# schematicv1_0.net
KiCad netlist of a schematic drawn in EAGLE
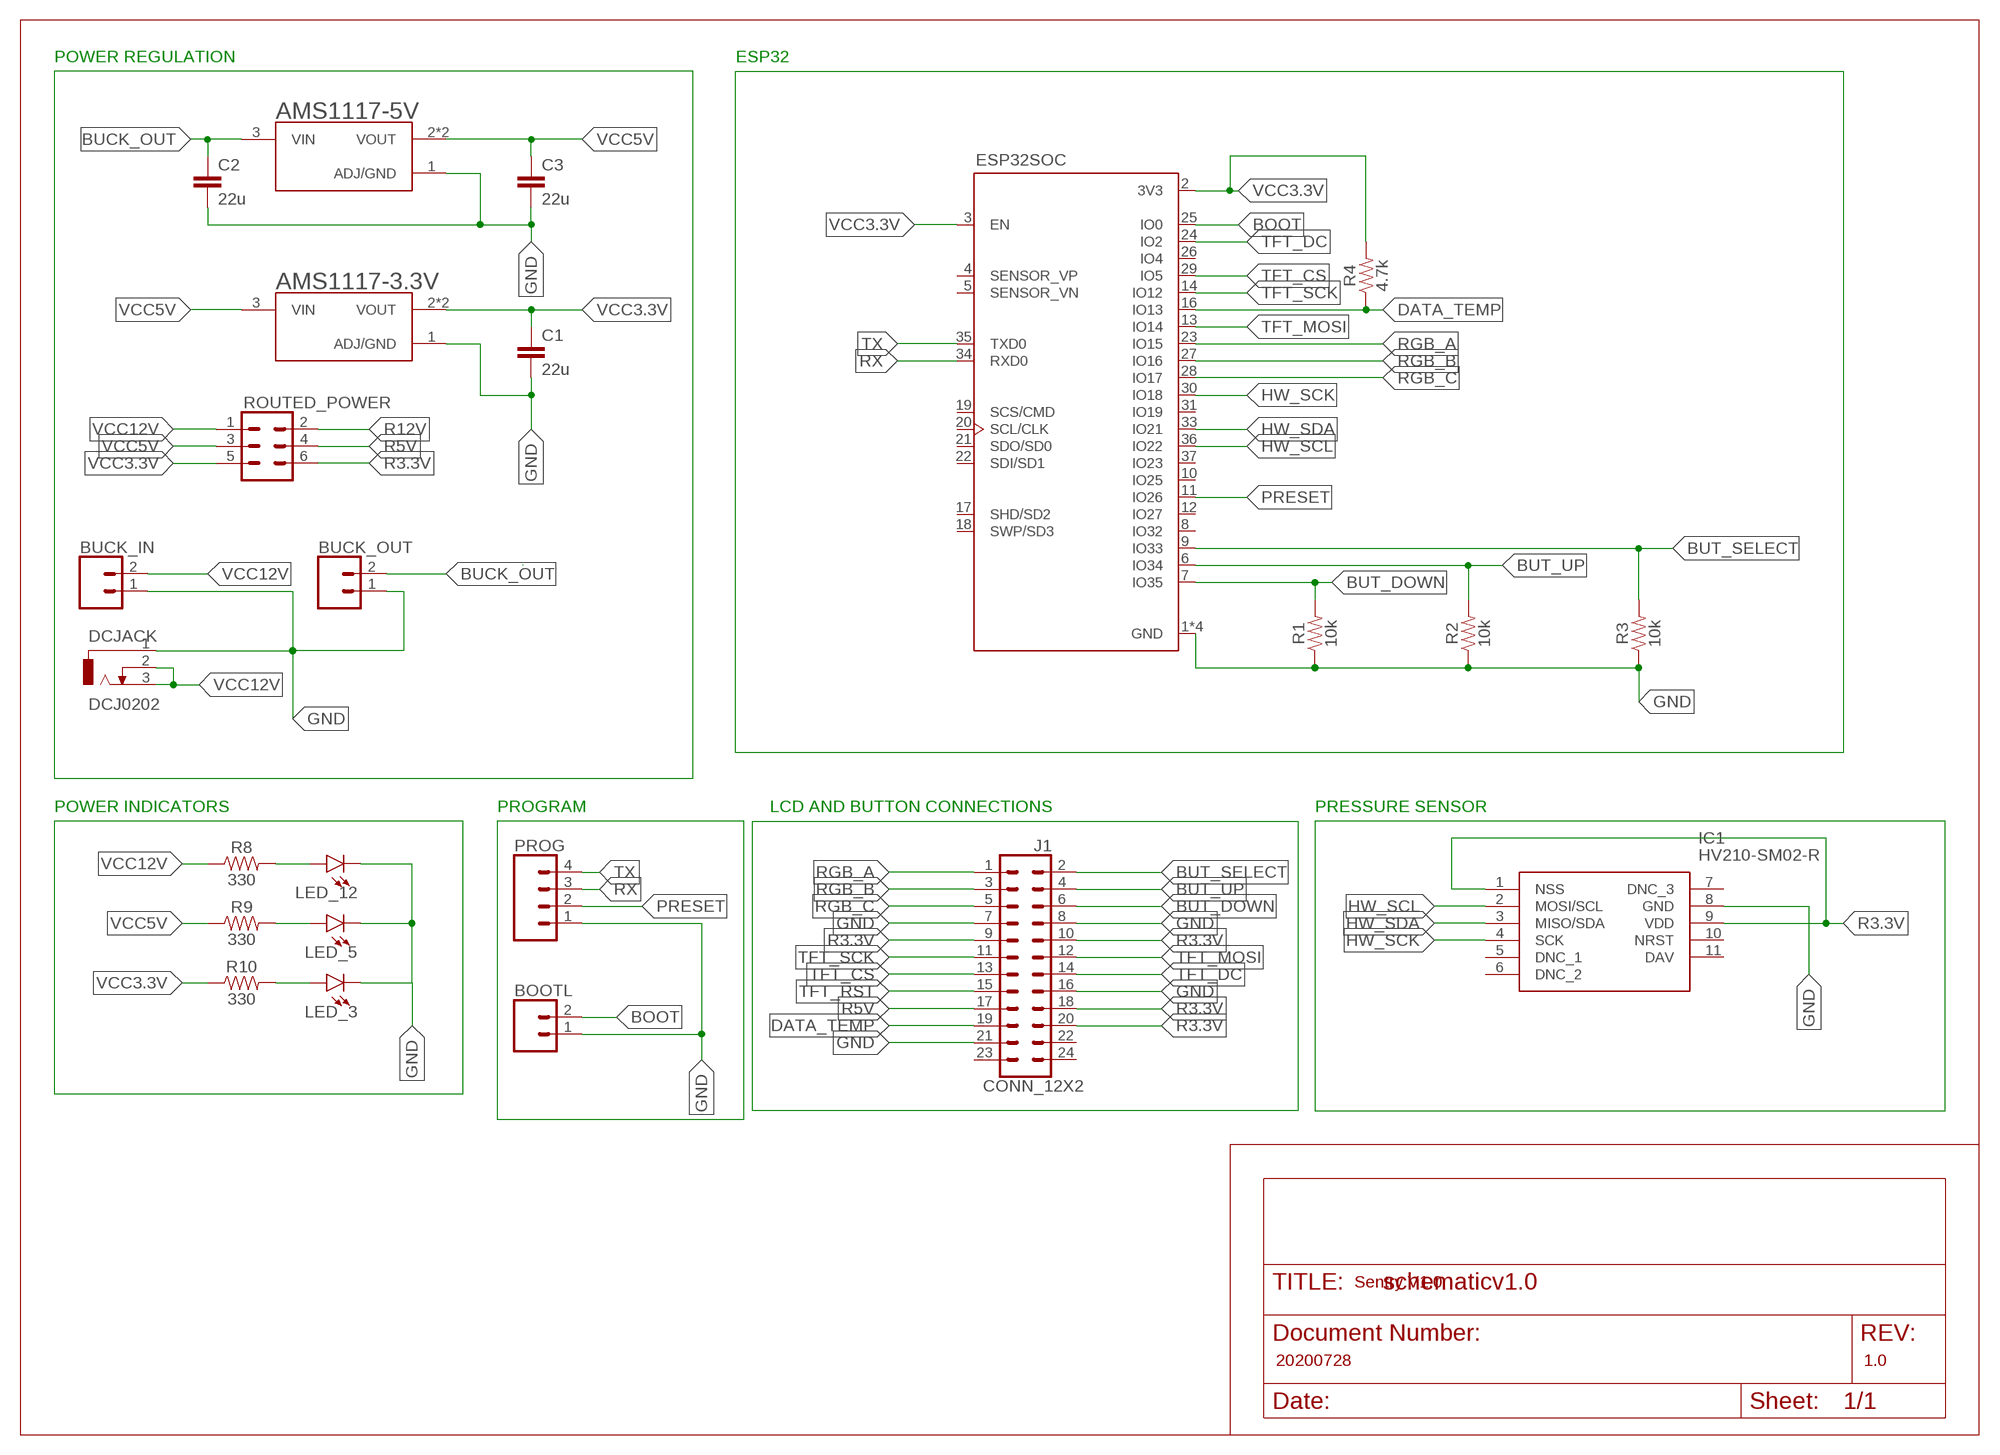
[diagram p0: schematic, sheet 1]

(export (version "E")
  (design (tool "Eeschema 10.0.6"))
  (components
    (comp (ref "AMS1117-3.3V")
      (value "AMS1117")
      (footprint "eagle-import:SOT229P700X180-4N")
      (fields (field (name "MF") "Seeed Technology"))
      (libsource (lib "eagle-import") (part "AMS1117"))
    )
    (comp (ref "AMS1117-5V")
      (value "AMS1117")
      (footprint "eagle-import:SOT229P700X180-4N")
      (fields (field (name "MF") "Seeed Technology"))
      (libsource (lib "eagle-import") (part "AMS1117"))
    )
    (comp (ref "BOOTL")
      (value "CONN_02")
      (footprint "eagle-import:1X02")
      (libsource (lib "eagle-import") (part "CONN_02"))
    )
    (comp (ref "BUCK_IN")
      (value "CONN_02")
      (footprint "eagle-import:1X02")
      (libsource (lib "eagle-import") (part "CONN_02"))
    )
    (comp (ref "BUCK_OUT")
      (value "CONN_02")
      (footprint "eagle-import:1X02")
      (libsource (lib "eagle-import") (part "CONN_02"))
    )
    (comp (ref "C1")
      (value "22u")
      (footprint "eagle-import:1206")
      (libsource (lib "eagle-import") (part "CAP-1206"))
    )
    (comp (ref "C2")
      (value "22u")
      (footprint "eagle-import:1206")
      (libsource (lib "eagle-import") (part "CAP-1206"))
    )
    (comp (ref "C3")
      (value "22u")
      (footprint "eagle-import:1206")
      (libsource (lib "eagle-import") (part "CAP-1206"))
    )
    (comp (ref "DCJACK")
      (value "DCJ0202")
      (footprint "eagle-import:DCJ0202")
      (libsource (lib "eagle-import") (part "DCJ0202"))
    )
    (comp (ref "ESP32SOC")
      (value "ESP32-WROOM-32D")
      (footprint "eagle-import:MODULE_ESP32-WROOM-32D")
      (fields (field (name "MF") "Espressif Systems"))
      (libsource (lib "eagle-import") (part "ESP32-WROOM-32D"))
    )
    (comp (ref "IC1")
      (value "HV210-SM02-R")
      (footprint "eagle-import:HV210SM02R")
      (fields (field (name "MOUSER_PART_NUMBER") "211-HV210-SM02-R"))
      (libsource (lib "eagle-import") (part "HV210-SM02-R"))
    )
    (comp (ref "J1")
      (value "CONN_12X2")
      (footprint "eagle-import:2X12")
      (libsource (lib "eagle-import") (part "CONN_12X2"))
    )
    (comp (ref "LED_3")
      (value "LED1206")
      (footprint "eagle-import:LED-1206")
      (libsource (lib "eagle-import") (part "LED1206"))
    )
    (comp (ref "LED_5")
      (value "LED1206")
      (footprint "eagle-import:LED-1206")
      (libsource (lib "eagle-import") (part "LED1206"))
    )
    (comp (ref "LED_12")
      (value "LED1206")
      (footprint "eagle-import:LED-1206")
      (libsource (lib "eagle-import") (part "LED1206"))
    )
    (comp (ref "PROG")
      (value "CONN_04PTH")
      (footprint "eagle-import:1X04")
      (libsource (lib "eagle-import") (part "CONN_04PTH"))
    )
    (comp (ref "R1")
      (value "10k")
      (footprint "eagle-import:1206")
      (libsource (lib "eagle-import") (part "RESISTOR1206"))
    )
    (comp (ref "R2")
      (value "10k")
      (footprint "eagle-import:1206")
      (libsource (lib "eagle-import") (part "RESISTOR1206"))
    )
    (comp (ref "R3")
      (value "10k")
      (footprint "eagle-import:1206")
      (libsource (lib "eagle-import") (part "RESISTOR1206"))
    )
    (comp (ref "R4")
      (value "4.7k")
      (footprint "eagle-import:1206")
      (libsource (lib "eagle-import") (part "RESISTOR1206"))
    )
    (comp (ref "R8")
      (value "330")
      (footprint "eagle-import:1206")
      (libsource (lib "eagle-import") (part "RESISTOR1206"))
    )
    (comp (ref "R9")
      (value "330")
      (footprint "eagle-import:1206")
      (libsource (lib "eagle-import") (part "RESISTOR1206"))
    )
    (comp (ref "R10")
      (value "330")
      (footprint "eagle-import:1206")
      (libsource (lib "eagle-import") (part "RESISTOR1206"))
    )
    (comp (ref "ROUTED_POWER")
      (value "CONN_03X2FEMALE")
      (footprint "eagle-import:2X3")
      (libsource (lib "eagle-import") (part "CONN_03X2FEMALE"))
    )
  )
  (nets
    (net (code "1") (name "BOOT") (class "Default")
      (node (ref "BOOTL") (pin "2") (pinfunction "2_2") (pintype "passive"))
      (node (ref "ESP32SOC") (pin "25") (pinfunction "IO0_25") (pintype "bidirectional"))
    )
    (net (code "2") (name "BUCK_OUT") (class "Default")
      (node (ref "AMS1117-5V") (pin "3") (pinfunction "VIN_3") (pintype "input"))
      (node (ref "BUCK_OUT") (pin "2") (pinfunction "2_2") (pintype "passive"))
      (node (ref "C2") (pin "1") (pinfunction "1_1") (pintype "passive"))
    )
    (net (code "3") (name "BUT_DOWN") (class "Default")
      (node (ref "ESP32SOC") (pin "7") (pinfunction "IO35_7") (pintype "bidirectional"))
      (node (ref "J1") (pin "6") (pinfunction "6_6") (pintype "passive"))
      (node (ref "R1") (pin "2") (pinfunction "2_2") (pintype "passive"))
    )
    (net (code "4") (name "BUT_SELECT") (class "Default")
      (node (ref "ESP32SOC") (pin "9") (pinfunction "IO33_9") (pintype "bidirectional"))
      (node (ref "J1") (pin "2") (pinfunction "2_2") (pintype "passive"))
      (node (ref "R3") (pin "2") (pinfunction "2_2") (pintype "passive"))
    )
    (net (code "5") (name "BUT_UP") (class "Default")
      (node (ref "ESP32SOC") (pin "6") (pinfunction "IO34_6") (pintype "bidirectional"))
      (node (ref "J1") (pin "4") (pinfunction "4_4") (pintype "passive"))
      (node (ref "R2") (pin "2") (pinfunction "2_2") (pintype "passive"))
    )
    (net (code "6") (name "DATA_TEMP") (class "Default")
      (node (ref "ESP32SOC") (pin "16") (pinfunction "IO13_16") (pintype "bidirectional"))
      (node (ref "J1") (pin "19") (pinfunction "19_19") (pintype "passive"))
      (node (ref "R4") (pin "1") (pinfunction "1_1") (pintype "passive"))
    )
    (net (code "7") (name "GND") (class "Default")
      (node (ref "AMS1117-3.3V") (pin "1") (pinfunction "ADJ/GND_1") (pintype "power_in"))
      (node (ref "AMS1117-5V") (pin "1") (pinfunction "ADJ/GND_1") (pintype "power_in"))
      (node (ref "BOOTL") (pin "1") (pinfunction "1_1") (pintype "passive"))
      (node (ref "BUCK_IN") (pin "1") (pinfunction "1_1") (pintype "passive"))
      (node (ref "BUCK_OUT") (pin "1") (pinfunction "1_1") (pintype "passive"))
      (node (ref "C1") (pin "2") (pinfunction "2_2") (pintype "passive"))
      (node (ref "C2") (pin "2") (pinfunction "2_2") (pintype "passive"))
      (node (ref "C3") (pin "2") (pinfunction "2_2") (pintype "passive"))
      (node (ref "DCJACK") (pin "1") (pinfunction "1_1") (pintype "passive"))
      (node (ref "ESP32SOC") (pin "1") (pinfunction "GND_1") (pintype "power_in"))
      (node (ref "ESP32SOC") (pin "15") (pinfunction "GND_15") (pintype "power_in"))
      (node (ref "ESP32SOC") (pin "38") (pinfunction "GND_38") (pintype "power_in"))
      (node (ref "ESP32SOC") (pin "39") (pinfunction "GND_39") (pintype "power_in"))
      (node (ref "IC1") (pin "8") (pinfunction "GND_8") (pintype "bidirectional"))
      (node (ref "J1") (pin "16") (pinfunction "16_16") (pintype "passive"))
      (node (ref "J1") (pin "21") (pinfunction "21_21") (pintype "passive"))
      (node (ref "J1") (pin "7") (pinfunction "7_7") (pintype "passive"))
      (node (ref "J1") (pin "8") (pinfunction "8_8") (pintype "passive"))
      (node (ref "LED_12") (pin "C") (pinfunction "C_C") (pintype "passive"))
      (node (ref "LED_3") (pin "C") (pinfunction "C_C") (pintype "passive"))
      (node (ref "LED_5") (pin "C") (pinfunction "C_C") (pintype "passive"))
      (node (ref "PROG") (pin "1") (pinfunction "1_1") (pintype "passive"))
      (node (ref "R1") (pin "1") (pinfunction "1_1") (pintype "passive"))
      (node (ref "R2") (pin "1") (pinfunction "1_1") (pintype "passive"))
      (node (ref "R3") (pin "1") (pinfunction "1_1") (pintype "passive"))
    )
    (net (code "8") (name "HW_SCK") (class "Default")
      (node (ref "ESP32SOC") (pin "30") (pinfunction "IO18_30") (pintype "bidirectional"))
      (node (ref "IC1") (pin "4") (pinfunction "SCK_4") (pintype "bidirectional"))
    )
    (net (code "9") (name "HW_SCL") (class "Default")
      (node (ref "ESP32SOC") (pin "36") (pinfunction "IO22_36") (pintype "bidirectional"))
      (node (ref "IC1") (pin "2") (pinfunction "MOSI/SCL_2") (pintype "bidirectional"))
    )
    (net (code "10") (name "HW_SDA") (class "Default")
      (node (ref "ESP32SOC") (pin "33") (pinfunction "IO21_33") (pintype "bidirectional"))
      (node (ref "IC1") (pin "3") (pinfunction "MISO/SDA_3") (pintype "bidirectional"))
    )
    (net (code "11") (name "Net-(LED_3-PadA)") (class "Default")
      (node (ref "LED_3") (pin "A") (pinfunction "A_A") (pintype "passive"))
      (node (ref "R10") (pin "2") (pinfunction "2_2") (pintype "passive"))
    )
    (net (code "12") (name "Net-(LED_5-PadA)") (class "Default")
      (node (ref "LED_5") (pin "A") (pinfunction "A_A") (pintype "passive"))
      (node (ref "R9") (pin "2") (pinfunction "2_2") (pintype "passive"))
    )
    (net (code "13") (name "Net-(LED_12-PadA)") (class "Default")
      (node (ref "LED_12") (pin "A") (pinfunction "A_A") (pintype "passive"))
      (node (ref "R8") (pin "2") (pinfunction "2_2") (pintype "passive"))
    )
    (net (code "14") (name "PRESET") (class "Default")
      (node (ref "ESP32SOC") (pin "11") (pinfunction "IO26_11") (pintype "bidirectional"))
      (node (ref "PROG") (pin "2") (pinfunction "2_2") (pintype "passive"))
    )
    (net (code "15") (name "R3.3V") (class "Default")
      (node (ref "IC1") (pin "1") (pinfunction "NSS_1") (pintype "bidirectional"))
      (node (ref "IC1") (pin "9") (pinfunction "VDD_9") (pintype "bidirectional"))
      (node (ref "J1") (pin "10") (pinfunction "10_10") (pintype "passive"))
      (node (ref "J1") (pin "18") (pinfunction "18_18") (pintype "passive"))
      (node (ref "J1") (pin "20") (pinfunction "20_20") (pintype "passive"))
      (node (ref "J1") (pin "9") (pinfunction "9_9") (pintype "passive"))
      (node (ref "ROUTED_POWER") (pin "6") (pinfunction "6_6") (pintype "bidirectional"))
    )
    (net (code "16") (name "R5V") (class "Default")
      (node (ref "J1") (pin "17") (pinfunction "17_17") (pintype "passive"))
      (node (ref "ROUTED_POWER") (pin "4") (pinfunction "4_4") (pintype "bidirectional"))
    )
    (net (code "17") (name "R12V") (class "Default")
      (node (ref "ROUTED_POWER") (pin "2") (pinfunction "2_2") (pintype "bidirectional"))
    )
    (net (code "18") (name "RGB_A") (class "Default")
      (node (ref "ESP32SOC") (pin "23") (pinfunction "IO15_23") (pintype "bidirectional"))
      (node (ref "J1") (pin "1") (pinfunction "1_1") (pintype "passive"))
    )
    (net (code "19") (name "RGB_B") (class "Default")
      (node (ref "ESP32SOC") (pin "27") (pinfunction "IO16_27") (pintype "bidirectional"))
      (node (ref "J1") (pin "3") (pinfunction "3_3") (pintype "passive"))
    )
    (net (code "20") (name "RGB_C") (class "Default")
      (node (ref "ESP32SOC") (pin "28") (pinfunction "IO17_28") (pintype "bidirectional"))
      (node (ref "J1") (pin "5") (pinfunction "5_5") (pintype "passive"))
    )
    (net (code "21") (name "RX") (class "Default")
      (node (ref "ESP32SOC") (pin "34") (pinfunction "RXD0_34") (pintype "bidirectional"))
      (node (ref "PROG") (pin "3") (pinfunction "3_3") (pintype "passive"))
    )
    (net (code "22") (name "TFT_CS") (class "Default")
      (node (ref "ESP32SOC") (pin "29") (pinfunction "IO5_29") (pintype "bidirectional"))
      (node (ref "J1") (pin "13") (pinfunction "13_13") (pintype "passive"))
    )
    (net (code "23") (name "TFT_DC") (class "Default")
      (node (ref "ESP32SOC") (pin "24") (pinfunction "IO2_24") (pintype "bidirectional"))
      (node (ref "J1") (pin "14") (pinfunction "14_14") (pintype "passive"))
    )
    (net (code "24") (name "TFT_MOSI") (class "Default")
      (node (ref "ESP32SOC") (pin "13") (pinfunction "IO14_13") (pintype "bidirectional"))
      (node (ref "J1") (pin "12") (pinfunction "12_12") (pintype "passive"))
    )
    (net (code "25") (name "TFT_RST") (class "Default")
      (node (ref "J1") (pin "15") (pinfunction "15_15") (pintype "passive"))
    )
    (net (code "26") (name "TFT_SCK") (class "Default")
      (node (ref "ESP32SOC") (pin "14") (pinfunction "IO12_14") (pintype "bidirectional"))
      (node (ref "J1") (pin "11") (pinfunction "11_11") (pintype "passive"))
    )
    (net (code "27") (name "TX") (class "Default")
      (node (ref "ESP32SOC") (pin "35") (pinfunction "TXD0_35") (pintype "bidirectional"))
      (node (ref "PROG") (pin "4") (pinfunction "4_4") (pintype "passive"))
    )
    (net (code "28") (name "VCC3.3V") (class "Default")
      (node (ref "AMS1117-3.3V") (pin "2") (pinfunction "VOUT_2") (pintype "output"))
      (node (ref "AMS1117-3.3V") (pin "4") (pinfunction "VOUT_4") (pintype "output"))
      (node (ref "C1") (pin "1") (pinfunction "1_1") (pintype "passive"))
      (node (ref "ESP32SOC") (pin "2") (pinfunction "3V3_2") (pintype "power_in"))
      (node (ref "ESP32SOC") (pin "3") (pinfunction "EN_3") (pintype "input"))
      (node (ref "R10") (pin "1") (pinfunction "1_1") (pintype "passive"))
      (node (ref "R4") (pin "2") (pinfunction "2_2") (pintype "passive"))
      (node (ref "ROUTED_POWER") (pin "5") (pinfunction "5_5") (pintype "bidirectional"))
    )
    (net (code "29") (name "VCC5V") (class "Default")
      (node (ref "AMS1117-3.3V") (pin "3") (pinfunction "VIN_3") (pintype "input"))
      (node (ref "AMS1117-5V") (pin "2") (pinfunction "VOUT_2") (pintype "output"))
      (node (ref "AMS1117-5V") (pin "4") (pinfunction "VOUT_4") (pintype "output"))
      (node (ref "C3") (pin "1") (pinfunction "1_1") (pintype "passive"))
      (node (ref "R9") (pin "1") (pinfunction "1_1") (pintype "passive"))
      (node (ref "ROUTED_POWER") (pin "3") (pinfunction "3_3") (pintype "bidirectional"))
    )
    (net (code "30") (name "VCC12V") (class "Default")
      (node (ref "BUCK_IN") (pin "2") (pinfunction "2_2") (pintype "passive"))
      (node (ref "DCJACK") (pin "2") (pinfunction "2_2") (pintype "passive"))
      (node (ref "DCJACK") (pin "3") (pinfunction "3_3") (pintype "passive"))
      (node (ref "R8") (pin "1") (pinfunction "1_1") (pintype "passive"))
      (node (ref "ROUTED_POWER") (pin "1") (pinfunction "1_1") (pintype "bidirectional"))
    )
    (net (code "31") (name "unconnected-(ESP32SOC-IO4-Pad26)") (class "Default")
      (node (ref "ESP32SOC") (pin "26") (pinfunction "IO4_26") (pintype "bidirectional"))
    )
    (net (code "32") (name "unconnected-(ESP32SOC-IO19-Pad31)") (class "Default")
      (node (ref "ESP32SOC") (pin "31") (pinfunction "IO19_31") (pintype "bidirectional"))
    )
    (net (code "33") (name "unconnected-(ESP32SOC-IO23-Pad37)") (class "Default")
      (node (ref "ESP32SOC") (pin "37") (pinfunction "IO23_37") (pintype "bidirectional"))
    )
    (net (code "34") (name "unconnected-(ESP32SOC-IO25-Pad10)") (class "Default")
      (node (ref "ESP32SOC") (pin "10") (pinfunction "IO25_10") (pintype "bidirectional"))
    )
    (net (code "35") (name "unconnected-(ESP32SOC-IO27-Pad12)") (class "Default")
      (node (ref "ESP32SOC") (pin "12") (pinfunction "IO27_12") (pintype "bidirectional"))
    )
    (net (code "36") (name "unconnected-(ESP32SOC-IO32-Pad8)") (class "Default")
      (node (ref "ESP32SOC") (pin "8") (pinfunction "IO32_8") (pintype "bidirectional"))
    )
    (net (code "37") (name "unconnected-(ESP32SOC-SCL{slash}CLK-Pad20)") (class "Default")
      (node (ref "ESP32SOC") (pin "20") (pinfunction "SCL/CLK_20") (pintype "bidirectional"))
    )
    (net (code "38") (name "unconnected-(ESP32SOC-SCS{slash}CMD-Pad19)") (class "Default")
      (node (ref "ESP32SOC") (pin "19") (pinfunction "SCS/CMD_19") (pintype "bidirectional"))
    )
    (net (code "39") (name "unconnected-(ESP32SOC-SDI{slash}SD1-Pad22)") (class "Default")
      (node (ref "ESP32SOC") (pin "22") (pinfunction "SDI/SD1_22") (pintype "bidirectional"))
    )
    (net (code "40") (name "unconnected-(ESP32SOC-SDO{slash}SD0-Pad21)") (class "Default")
      (node (ref "ESP32SOC") (pin "21") (pinfunction "SDO/SD0_21") (pintype "bidirectional"))
    )
    (net (code "41") (name "unconnected-(ESP32SOC-SENSOR_VN-Pad5)") (class "Default")
      (node (ref "ESP32SOC") (pin "5") (pinfunction "SENSOR_VN_5") (pintype "input"))
    )
    (net (code "42") (name "unconnected-(ESP32SOC-SENSOR_VP-Pad4)") (class "Default")
      (node (ref "ESP32SOC") (pin "4") (pinfunction "SENSOR_VP_4") (pintype "input"))
    )
    (net (code "43") (name "unconnected-(ESP32SOC-SHD{slash}SD2-Pad17)") (class "Default")
      (node (ref "ESP32SOC") (pin "17") (pinfunction "SHD/SD2_17") (pintype "bidirectional"))
    )
    (net (code "44") (name "unconnected-(ESP32SOC-SWP{slash}SD3-Pad18)") (class "Default")
      (node (ref "ESP32SOC") (pin "18") (pinfunction "SWP/SD3_18") (pintype "bidirectional"))
    )
    (net (code "45") (name "unconnected-(IC1-DAV-Pad11)") (class "Default")
      (node (ref "IC1") (pin "11") (pinfunction "DAV_11") (pintype "bidirectional"))
    )
    (net (code "46") (name "unconnected-(IC1-DNC_1-Pad5)") (class "Default")
      (node (ref "IC1") (pin "5") (pinfunction "DNC_1_5") (pintype "bidirectional"))
    )
    (net (code "47") (name "unconnected-(IC1-DNC_2-Pad6)") (class "Default")
      (node (ref "IC1") (pin "6") (pinfunction "DNC_2_6") (pintype "bidirectional"))
    )
    (net (code "48") (name "unconnected-(IC1-DNC_3-Pad7)") (class "Default")
      (node (ref "IC1") (pin "7") (pinfunction "DNC_3_7") (pintype "bidirectional"))
    )
    (net (code "49") (name "unconnected-(IC1-NRST-Pad10)") (class "Default")
      (node (ref "IC1") (pin "10") (pinfunction "NRST_10") (pintype "bidirectional"))
    )
    (net (code "50") (name "unconnected-(J1-Pad22)") (class "Default")
      (node (ref "J1") (pin "22") (pinfunction "22_22") (pintype "passive"))
    )
    (net (code "51") (name "unconnected-(J1-Pad23)") (class "Default")
      (node (ref "J1") (pin "23") (pinfunction "23_23") (pintype "passive"))
    )
    (net (code "52") (name "unconnected-(J1-Pad24)") (class "Default")
      (node (ref "J1") (pin "24") (pinfunction "24_24") (pintype "passive"))
    )
  )
)
